# MAXIM-ADC1.net
KiCad netlist of a schematic drawn in Altium Designer
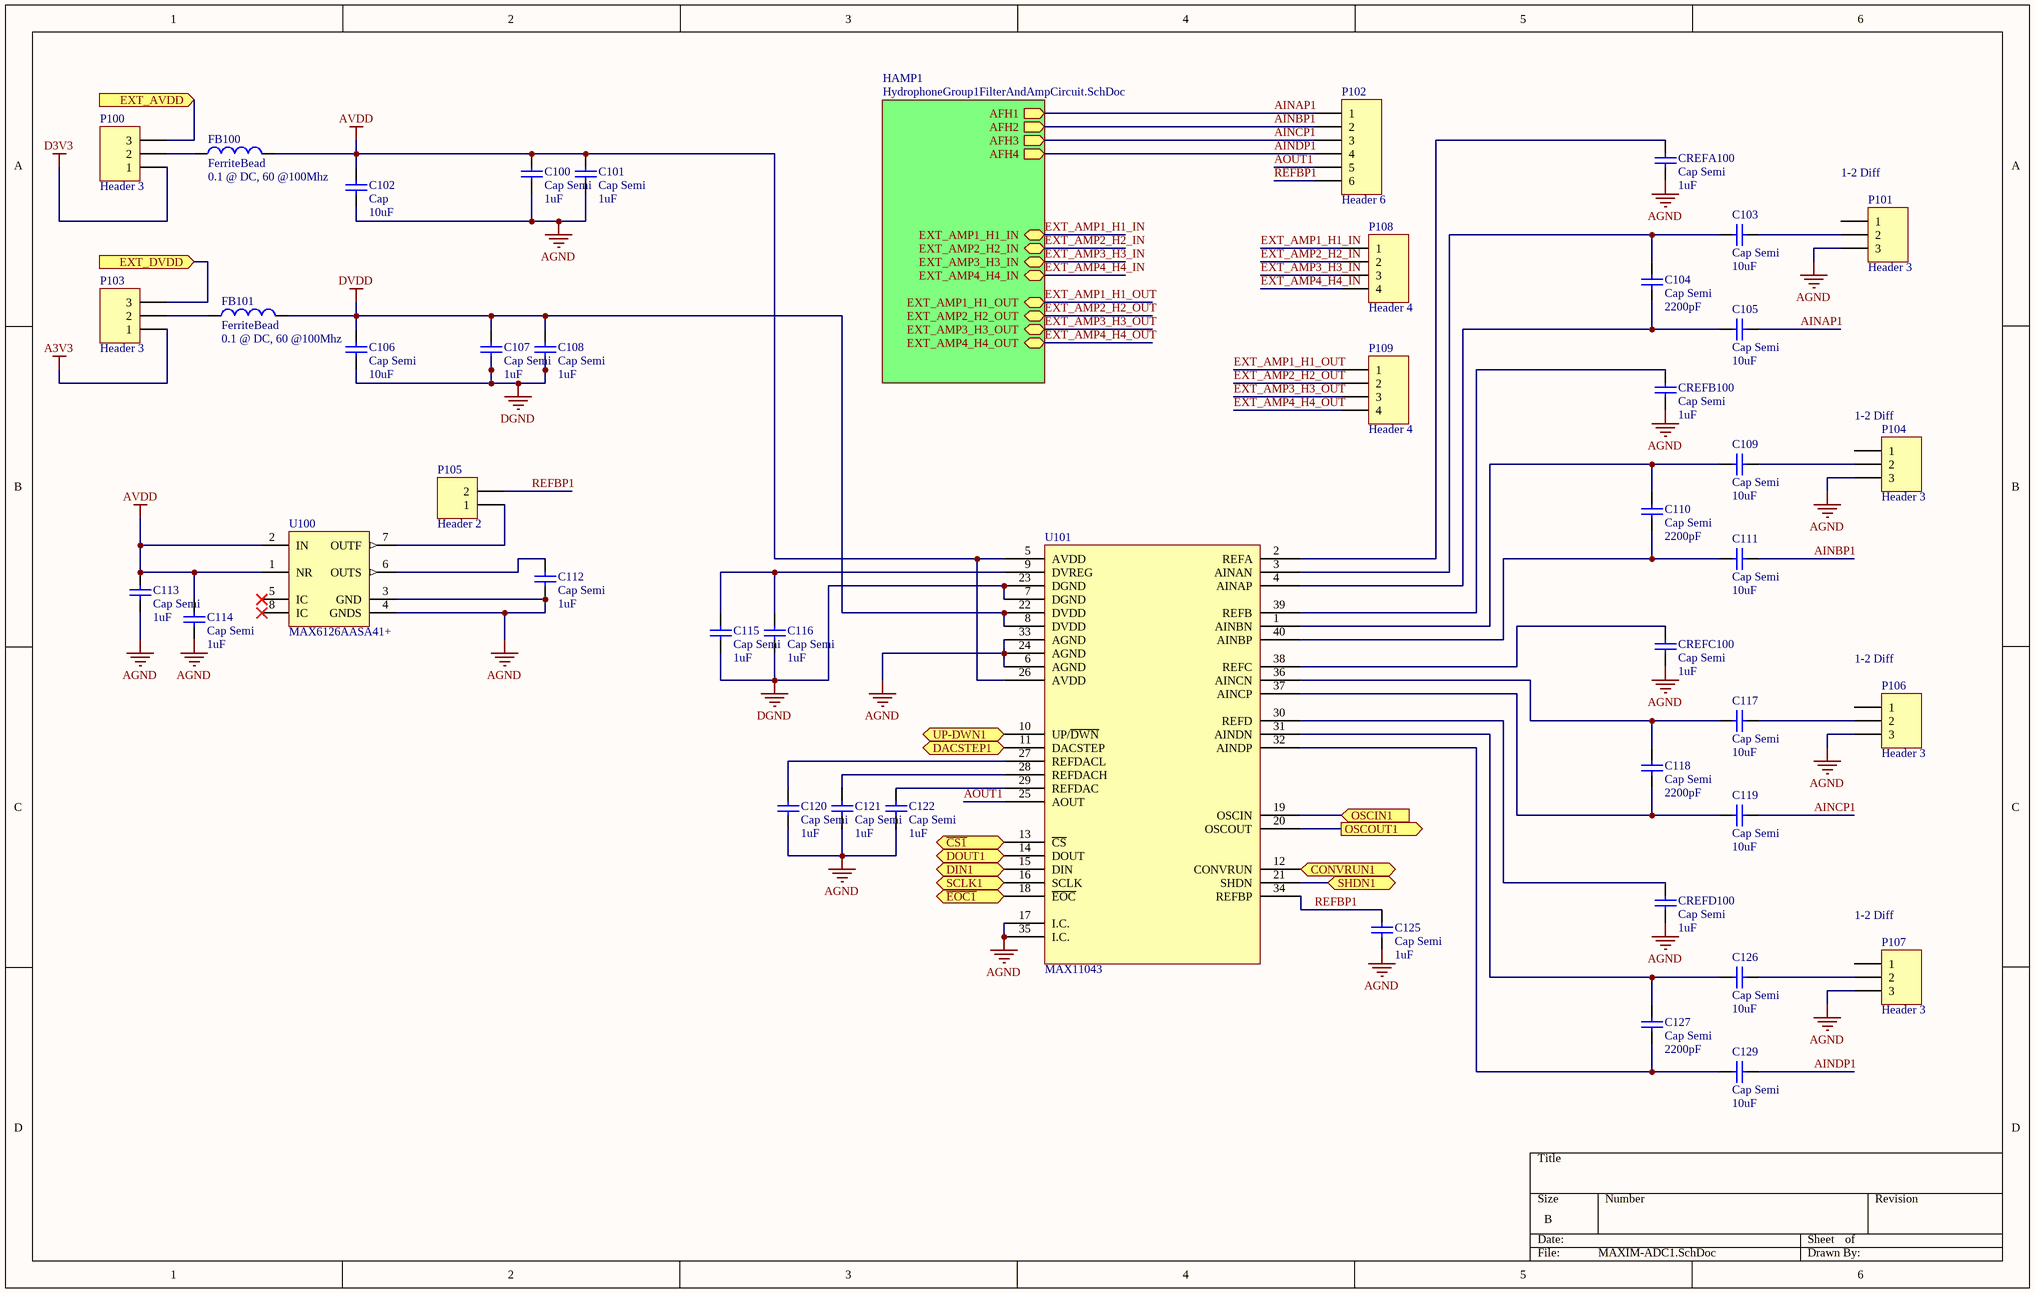
[diagram p0: MAXIM-ADC1.SchDoc]

(export (version "E")
  (design (tool "Eeschema 10.0.6"))
  (components
    (comp (ref "C100")
      (value "Cap Semi")
      (footprint "1608[0603]")
      (description "Capacitor (Semiconductor SIM Model)")
      (fields (field (name "ALTIUM_VALUE") "1uF") (field (name "PUBLISHER") "Altium Limited"))
      (libsource (lib "Miscellaneous Devices") (part "Cap Semi"))
    )
    (comp (ref "C101")
      (value "Cap Semi")
      (footprint "1608[0603]")
      (description "Capacitor (Semiconductor SIM Model)")
      (fields (field (name "ALTIUM_VALUE") "1uF") (field (name "PUBLISHER") "Altium Limited"))
      (libsource (lib "Miscellaneous Devices") (part "Cap Semi"))
    )
    (comp (ref "C102")
      (value "Cap")
      (footprint "1608[0603]")
      (description "Capacitor (Semiconductor SIM Model)")
      (fields (field (name "ALTIUM_VALUE") "10uF") (field (name "PUBLISHER") "Altium Limited"))
      (libsource (lib "Miscellaneous Devices") (part "Cap Semi"))
    )
    (comp (ref "C103")
      (value "Cap Semi")
      (footprint "1608[0603]")
      (description "Capacitor (Semiconductor SIM Model)")
      (fields (field (name "ALTIUM_VALUE") "10uF") (field (name "PUBLISHER") "Altium Limited"))
      (libsource (lib "Miscellaneous Devices") (part "Cap Semi"))
    )
    (comp (ref "C104")
      (value "Cap Semi")
      (footprint "1608[0603]")
      (description "Capacitor (Semiconductor SIM Model)")
      (fields (field (name "ALTIUM_VALUE") "2200pF") (field (name "PUBLISHER") "Altium Limited"))
      (libsource (lib "Miscellaneous Devices") (part "Cap Semi"))
    )
    (comp (ref "C105")
      (value "Cap Semi")
      (footprint "1608[0603]")
      (description "Capacitor (Semiconductor SIM Model)")
      (fields (field (name "ALTIUM_VALUE") "10uF") (field (name "PUBLISHER") "Altium Limited"))
      (libsource (lib "Miscellaneous Devices") (part "Cap Semi"))
    )
    (comp (ref "C106")
      (value "Cap Semi")
      (footprint "C1206")
      (description "Capacitor (Semiconductor SIM Model)")
      (fields (field (name "ALTIUM_VALUE") "10uF") (field (name "PUBLISHER") "Altium Limited"))
      (libsource (lib "Miscellaneous Devices") (part "Cap Semi"))
    )
    (comp (ref "C107")
      (value "Cap Semi")
      (footprint "1608[0603]")
      (description "Capacitor (Semiconductor SIM Model)")
      (fields (field (name "ALTIUM_VALUE") "1uF") (field (name "PUBLISHER") "Altium Limited"))
      (libsource (lib "Miscellaneous Devices") (part "Cap Semi"))
    )
    (comp (ref "C108")
      (value "Cap Semi")
      (footprint "C1206")
      (description "Capacitor (Semiconductor SIM Model)")
      (fields (field (name "ALTIUM_VALUE") "1uF") (field (name "PUBLISHER") "Altium Limited"))
      (libsource (lib "Miscellaneous Devices") (part "Cap Semi"))
    )
    (comp (ref "C109")
      (value "Cap Semi")
      (footprint "1608[0603]")
      (description "Capacitor (Semiconductor SIM Model)")
      (fields (field (name "ALTIUM_VALUE") "10uF") (field (name "PUBLISHER") "Altium Limited"))
      (libsource (lib "Miscellaneous Devices") (part "Cap Semi"))
    )
    (comp (ref "C110")
      (value "Cap Semi")
      (footprint "1608[0603]")
      (description "Capacitor (Semiconductor SIM Model)")
      (fields (field (name "ALTIUM_VALUE") "2200pF") (field (name "PUBLISHER") "Altium Limited"))
      (libsource (lib "Miscellaneous Devices") (part "Cap Semi"))
    )
    (comp (ref "C111")
      (value "Cap Semi")
      (footprint "1608[0603]")
      (description "Capacitor (Semiconductor SIM Model)")
      (fields (field (name "ALTIUM_VALUE") "10uF") (field (name "PUBLISHER") "Altium Limited"))
      (libsource (lib "Miscellaneous Devices") (part "Cap Semi"))
    )
    (comp (ref "C112")
      (value "Cap Semi")
      (footprint "1608[0603]")
      (description "Capacitor (Semiconductor SIM Model)")
      (fields (field (name "ALTIUM_VALUE") "1uF") (field (name "PUBLISHER") "Altium Limited"))
      (libsource (lib "Miscellaneous Devices") (part "Cap Semi"))
    )
    (comp (ref "C113")
      (value "Cap Semi")
      (footprint "1608[0603]")
      (description "Capacitor (Semiconductor SIM Model)")
      (fields (field (name "ALTIUM_VALUE") "1uF") (field (name "PUBLISHER") "Altium Limited"))
      (libsource (lib "Miscellaneous Devices") (part "Cap Semi"))
    )
    (comp (ref "C114")
      (value "Cap Semi")
      (footprint "1608[0603]")
      (description "Capacitor (Semiconductor SIM Model)")
      (fields (field (name "ALTIUM_VALUE") "1uF") (field (name "PUBLISHER") "Altium Limited"))
      (libsource (lib "Miscellaneous Devices") (part "Cap Semi"))
    )
    (comp (ref "C115")
      (value "Cap Semi")
      (footprint "1608[0603]")
      (description "Capacitor (Semiconductor SIM Model)")
      (fields (field (name "ALTIUM_VALUE") "1uF") (field (name "PUBLISHER") "Altium Limited"))
      (libsource (lib "Miscellaneous Devices") (part "Cap Semi"))
    )
    (comp (ref "C116")
      (value "Cap Semi")
      (footprint "1608[0603]")
      (description "Capacitor (Semiconductor SIM Model)")
      (fields (field (name "ALTIUM_VALUE") "1uF") (field (name "PUBLISHER") "Altium Limited"))
      (libsource (lib "Miscellaneous Devices") (part "Cap Semi"))
    )
    (comp (ref "C117")
      (value "Cap Semi")
      (footprint "1608[0603]")
      (description "Capacitor (Semiconductor SIM Model)")
      (fields (field (name "ALTIUM_VALUE") "10uF") (field (name "PUBLISHER") "Altium Limited"))
      (libsource (lib "Miscellaneous Devices") (part "Cap Semi"))
    )
    (comp (ref "C118")
      (value "Cap Semi")
      (footprint "1608[0603]")
      (description "Capacitor (Semiconductor SIM Model)")
      (fields (field (name "ALTIUM_VALUE") "2200pF") (field (name "PUBLISHER") "Altium Limited"))
      (libsource (lib "Miscellaneous Devices") (part "Cap Semi"))
    )
    (comp (ref "C119")
      (value "Cap Semi")
      (footprint "1608[0603]")
      (description "Capacitor (Semiconductor SIM Model)")
      (fields (field (name "ALTIUM_VALUE") "10uF") (field (name "PUBLISHER") "Altium Limited"))
      (libsource (lib "Miscellaneous Devices") (part "Cap Semi"))
    )
    (comp (ref "C120")
      (value "Cap Semi")
      (footprint "1608[0603]")
      (description "Capacitor (Semiconductor SIM Model)")
      (fields (field (name "ALTIUM_VALUE") "1uF") (field (name "PUBLISHER") "Altium Limited"))
      (libsource (lib "Miscellaneous Devices") (part "Cap Semi"))
    )
    (comp (ref "C121")
      (value "Cap Semi")
      (footprint "1608[0603]")
      (description "Capacitor (Semiconductor SIM Model)")
      (fields (field (name "ALTIUM_VALUE") "1uF") (field (name "PUBLISHER") "Altium Limited"))
      (libsource (lib "Miscellaneous Devices") (part "Cap Semi"))
    )
    (comp (ref "C122")
      (value "Cap Semi")
      (footprint "1608[0603]")
      (description "Capacitor (Semiconductor SIM Model)")
      (fields (field (name "ALTIUM_VALUE") "1uF") (field (name "PUBLISHER") "Altium Limited"))
      (libsource (lib "Miscellaneous Devices") (part "Cap Semi"))
    )
    (comp (ref "C125")
      (value "Cap Semi")
      (footprint "1608[0603]")
      (description "Capacitor (Semiconductor SIM Model)")
      (fields (field (name "ALTIUM_VALUE") "1uF") (field (name "PUBLISHER") "Altium Limited"))
      (libsource (lib "Miscellaneous Devices") (part "Cap Semi"))
    )
    (comp (ref "C126")
      (value "Cap Semi")
      (footprint "1608[0603]")
      (description "Capacitor (Semiconductor SIM Model)")
      (fields (field (name "ALTIUM_VALUE") "10uF") (field (name "PUBLISHER") "Altium Limited"))
      (libsource (lib "Miscellaneous Devices") (part "Cap Semi"))
    )
    (comp (ref "C127")
      (value "Cap Semi")
      (footprint "1608[0603]")
      (description "Capacitor (Semiconductor SIM Model)")
      (fields (field (name "ALTIUM_VALUE") "2200pF") (field (name "PUBLISHER") "Altium Limited"))
      (libsource (lib "Miscellaneous Devices") (part "Cap Semi"))
    )
    (comp (ref "C129")
      (value "Cap Semi")
      (footprint "1608[0603]")
      (description "Capacitor (Semiconductor SIM Model)")
      (fields (field (name "ALTIUM_VALUE") "10uF") (field (name "PUBLISHER") "Altium Limited"))
      (libsource (lib "Miscellaneous Devices") (part "Cap Semi"))
    )
    (comp (ref "CREFA100")
      (value "Cap Semi")
      (footprint "1608[0603]")
      (description "Capacitor (Semiconductor SIM Model)")
      (fields (field (name "ALTIUM_VALUE") "1uF") (field (name "PUBLISHER") "Altium Limited"))
      (libsource (lib "Miscellaneous Devices") (part "Cap Semi"))
    )
    (comp (ref "CREFB100")
      (value "Cap Semi")
      (footprint "1608[0603]")
      (description "Capacitor (Semiconductor SIM Model)")
      (fields (field (name "ALTIUM_VALUE") "1uF") (field (name "PUBLISHER") "Altium Limited"))
      (libsource (lib "Miscellaneous Devices") (part "Cap Semi"))
    )
    (comp (ref "CREFC100")
      (value "Cap Semi")
      (footprint "1608[0603]")
      (description "Capacitor (Semiconductor SIM Model)")
      (fields (field (name "ALTIUM_VALUE") "1uF") (field (name "PUBLISHER") "Altium Limited"))
      (libsource (lib "Miscellaneous Devices") (part "Cap Semi"))
    )
    (comp (ref "CREFD100")
      (value "Cap Semi")
      (footprint "1608[0603]")
      (description "Capacitor (Semiconductor SIM Model)")
      (fields (field (name "ALTIUM_VALUE") "1uF") (field (name "PUBLISHER") "Altium Limited"))
      (libsource (lib "Miscellaneous Devices") (part "Cap Semi"))
    )
    (comp (ref "FB100")
      (value "FerriteBead")
      (footprint "0603")
      (description "Inductor")
      (fields
        (field (name "ALTIUM_VALUE") "0.1 @ DC, 60 @100Mhz")
        (field (name "PUBLISHER") "Altium Limited")
      )
      (libsource (lib "Miscellaneous Devices") (part "Inductor"))
    )
    (comp (ref "FB101")
      (value "FerriteBead")
      (footprint "0603")
      (description "Inductor")
      (fields
        (field (name "ALTIUM_VALUE") "0.1 @ DC, 60 @100Mhz")
        (field (name "PUBLISHER") "Altium Limited")
      )
      (libsource (lib "Miscellaneous Devices") (part "Inductor"))
    )
    (comp (ref "P100")
      (value "Header 3")
      (footprint "HDR1X3")
      (description "Header, 3-Pin")
      (fields (field (name "PUBLISHER") "Altium Limited"))
      (libsource (lib "") (part "Header 3_1"))
    )
    (comp (ref "P101")
      (value "Header 3")
      (footprint "HDR1X3")
      (description "Header, 3-Pin")
      (fields (field (name "PUBLISHER") "Altium Limited"))
      (libsource (lib "Miscellaneous Connectors") (part "Header 3"))
    )
    (comp (ref "P102")
      (value "Header 6")
      (footprint "HDR1X6")
      (description "Header, 6-Pin")
      (fields (field (name "PUBLISHER") "Altium Limited"))
      (libsource (lib "Miscellaneous Connectors") (part "Header 6"))
    )
    (comp (ref "P103")
      (value "Header 3")
      (footprint "HDR1X3")
      (description "Header, 3-Pin")
      (fields (field (name "PUBLISHER") "Altium Limited"))
      (libsource (lib "") (part "Header 3_1"))
    )
    (comp (ref "P104")
      (value "Header 3")
      (footprint "HDR1X3")
      (description "Header, 3-Pin")
      (fields (field (name "PUBLISHER") "Altium Limited"))
      (libsource (lib "Miscellaneous Connectors") (part "Header 3"))
    )
    (comp (ref "P105")
      (value "Header 2")
      (footprint "HDR1X2")
      (description "Header, 2-Pin")
      (fields (field (name "PUBLISHER") "Altium Limited"))
      (libsource (lib "Miscellaneous Connectors") (part "Header 2"))
    )
    (comp (ref "P106")
      (value "Header 3")
      (footprint "HDR1X3")
      (description "Header, 3-Pin")
      (fields (field (name "PUBLISHER") "Altium Limited"))
      (libsource (lib "Miscellaneous Connectors") (part "Header 3"))
    )
    (comp (ref "P107")
      (value "Header 3")
      (footprint "HDR1X3")
      (description "Header, 3-Pin")
      (fields (field (name "PUBLISHER") "Altium Limited"))
      (libsource (lib "Miscellaneous Connectors") (part "Header 3"))
    )
    (comp (ref "P108")
      (value "Header 4")
      (footprint "HDR1X4")
      (description "Header, 4-Pin")
      (fields (field (name "PUBLISHER") "Altium Limited"))
      (libsource (lib "Miscellaneous Connectors") (part "Header 4"))
    )
    (comp (ref "P109")
      (value "Header 4")
      (footprint "HDR1X4")
      (description "Header, 4-Pin")
      (fields (field (name "PUBLISHER") "Altium Limited"))
      (libsource (lib "Miscellaneous Connectors") (part "Header 4"))
    )
    (comp (ref "U100")
      (value "MAX6126AASA41+")
      (footprint "MAXM-S8+4_L")
      (fields (field (name "MANUFACTURER") "Maxim"))
      (libsource (lib "Altium Content Vault") (part "CMP-0977-00016-1"))
    )
    (comp (ref "U101")
      (value "MAX11043")
      (footprint "QFN50P600X600X80_HS-41N")
      (libsource (lib "Max11043") (part "MAX11043"))
    )
  )
  (nets
    (net (code "1") (name "/AINAP1") (class "Default")
      (node (ref "C105") (pin "1") (pinfunction "1_1") (pintype "passive"))
      (node (ref "P102") (pin "1") (pinfunction "1_1") (pintype "passive"))
    )
    (net (code "2") (name "/AINBP1") (class "Default")
      (node (ref "C111") (pin "1") (pinfunction "1_1") (pintype "passive"))
      (node (ref "P102") (pin "2") (pinfunction "2_2") (pintype "passive"))
    )
    (net (code "3") (name "/AINCP1") (class "Default")
      (node (ref "C119") (pin "1") (pinfunction "1_1") (pintype "passive"))
      (node (ref "P102") (pin "3") (pinfunction "3_3") (pintype "passive"))
    )
    (net (code "4") (name "/AINDP1") (class "Default")
      (node (ref "C129") (pin "1") (pinfunction "1_1") (pintype "passive"))
      (node (ref "P102") (pin "4") (pinfunction "4_4") (pintype "passive"))
    )
    (net (code "5") (name "/AOUT1") (class "Default")
      (node (ref "P102") (pin "5") (pinfunction "5_5") (pintype "passive"))
      (node (ref "U101") (pin "25") (pinfunction "AOUT_25") (pintype "passive"))
    )
    (net (code "6") (name "/CONVRUN1") (class "Default")
      (node (ref "U101") (pin "12") (pinfunction "CONVRUN_12") (pintype "passive"))
    )
    (net (code "7") (name "/DACSTEP1") (class "Default")
      (node (ref "U101") (pin "11") (pinfunction "DACSTEP_11") (pintype "passive"))
    )
    (net (code "8") (name "/DIN1") (class "Default")
      (node (ref "U101") (pin "15") (pinfunction "DIN_15") (pintype "passive"))
    )
    (net (code "9") (name "/DOUT1") (class "Default")
      (node (ref "U101") (pin "14") (pinfunction "DOUT_14") (pintype "passive"))
    )
    (net (code "10") (name "/EXT_AMP1_H1_IN") (class "Default")
      (node (ref "P108") (pin "1") (pinfunction "1_1") (pintype "passive"))
    )
    (net (code "11") (name "/EXT_AMP1_H1_OUT") (class "Default")
      (node (ref "P109") (pin "1") (pinfunction "1_1") (pintype "passive"))
    )
    (net (code "12") (name "/EXT_AMP2_H2_IN") (class "Default")
      (node (ref "P108") (pin "2") (pinfunction "2_2") (pintype "passive"))
    )
    (net (code "13") (name "/EXT_AMP2_H2_OUT") (class "Default")
      (node (ref "P109") (pin "2") (pinfunction "2_2") (pintype "passive"))
    )
    (net (code "14") (name "/EXT_AMP3_H3_IN") (class "Default")
      (node (ref "P108") (pin "3") (pinfunction "3_3") (pintype "passive"))
    )
    (net (code "15") (name "/EXT_AMP3_H3_OUT") (class "Default")
      (node (ref "P109") (pin "3") (pinfunction "3_3") (pintype "passive"))
    )
    (net (code "16") (name "/EXT_AMP4_H4_IN") (class "Default")
      (node (ref "P108") (pin "4") (pinfunction "4_4") (pintype "passive"))
    )
    (net (code "17") (name "/EXT_AMP4_H4_OUT") (class "Default")
      (node (ref "P109") (pin "4") (pinfunction "4_4") (pintype "passive"))
    )
    (net (code "18") (name "/EXT_AVDD") (class "Default")
      (node (ref "P100") (pin "3") (pinfunction "3_3") (pintype "passive"))
    )
    (net (code "19") (name "/EXT_DVDD") (class "Default")
      (node (ref "P103") (pin "3") (pinfunction "3_3") (pintype "passive"))
    )
    (net (code "20") (name "/OSCIN1") (class "Default")
      (node (ref "U101") (pin "19") (pinfunction "OSCIN_19") (pintype "passive"))
    )
    (net (code "21") (name "/OSCOUT1") (class "Default")
      (node (ref "U101") (pin "20") (pinfunction "OSCOUT_20") (pintype "passive"))
    )
    (net (code "22") (name "/REFBP1") (class "Default")
      (node (ref "C125") (pin "1") (pinfunction "1_1") (pintype "passive"))
      (node (ref "P102") (pin "6") (pinfunction "6_6") (pintype "passive"))
      (node (ref "P105") (pin "2") (pinfunction "2_2") (pintype "passive"))
      (node (ref "U101") (pin "34") (pinfunction "REFBP_34") (pintype "passive"))
    )
    (net (code "23") (name "/SCLK1") (class "Default")
      (node (ref "U101") (pin "16") (pinfunction "SCLK_16") (pintype "passive"))
    )
    (net (code "24") (name "/SHDN1") (class "Default")
      (node (ref "U101") (pin "21") (pinfunction "SHDN_21") (pintype "passive"))
    )
    (net (code "25") (name "/UP-DWN1") (class "Default")
      (node (ref "U101") (pin "10") (pinfunction "UP/~{DWN}_10") (pintype "passive"))
    )
    (net (code "26") (name "/~{CS1}") (class "Default")
      (node (ref "U101") (pin "13") (pinfunction "~{CS}_13") (pintype "passive"))
    )
    (net (code "27") (name "/~{EOC1}") (class "Default")
      (node (ref "U101") (pin "18") (pinfunction "~{EOC}_18") (pintype "passive"))
    )
    (net (code "28") (name "A3V3") (class "Default")
      (node (ref "P103") (pin "1") (pinfunction "1_1") (pintype "passive"))
    )
    (net (code "29") (name "AGND") (class "Default")
      (node (ref "C100") (pin "2") (pinfunction "2_2") (pintype "passive"))
      (node (ref "C101") (pin "2") (pinfunction "2_2") (pintype "passive"))
      (node (ref "C102") (pin "2") (pinfunction "2_2") (pintype "passive"))
      (node (ref "C112") (pin "2") (pinfunction "2_2") (pintype "passive"))
      (node (ref "C113") (pin "2") (pinfunction "2_2") (pintype "passive"))
      (node (ref "C114") (pin "2") (pinfunction "2_2") (pintype "passive"))
      (node (ref "C120") (pin "1") (pinfunction "1_1") (pintype "passive"))
      (node (ref "C121") (pin "2") (pinfunction "2_2") (pintype "passive"))
      (node (ref "C122") (pin "1") (pinfunction "1_1") (pintype "passive"))
      (node (ref "C125") (pin "2") (pinfunction "2_2") (pintype "passive"))
      (node (ref "CREFA100") (pin "1") (pinfunction "1_1") (pintype "passive"))
      (node (ref "CREFB100") (pin "1") (pinfunction "1_1") (pintype "passive"))
      (node (ref "CREFC100") (pin "1") (pinfunction "1_1") (pintype "passive"))
      (node (ref "CREFD100") (pin "1") (pinfunction "1_1") (pintype "passive"))
      (node (ref "P101") (pin "3") (pinfunction "3_3") (pintype "passive"))
      (node (ref "P104") (pin "3") (pinfunction "3_3") (pintype "passive"))
      (node (ref "P106") (pin "3") (pinfunction "3_3") (pintype "passive"))
      (node (ref "P107") (pin "3") (pinfunction "3_3") (pintype "passive"))
      (node (ref "U100") (pin "3") (pinfunction "GND_3") (pintype "power_in"))
      (node (ref "U100") (pin "4") (pinfunction "GNDS_4") (pintype "power_in"))
      (node (ref "U101") (pin "17") (pinfunction "I.C._17") (pintype "passive"))
      (node (ref "U101") (pin "24") (pinfunction "AGND_24") (pintype "passive"))
      (node (ref "U101") (pin "33") (pinfunction "AGND_33") (pintype "passive"))
      (node (ref "U101") (pin "35") (pinfunction "I.C._35") (pintype "passive"))
      (node (ref "U101") (pin "6") (pinfunction "AGND_6") (pintype "passive"))
    )
    (net (code "30") (name "AVDD") (class "Default")
      (node (ref "C100") (pin "1") (pinfunction "1_1") (pintype "passive"))
      (node (ref "C101") (pin "1") (pinfunction "1_1") (pintype "passive"))
      (node (ref "C102") (pin "1") (pinfunction "1_1") (pintype "passive"))
      (node (ref "C113") (pin "1") (pinfunction "1_1") (pintype "passive"))
      (node (ref "C114") (pin "1") (pinfunction "1_1") (pintype "passive"))
      (node (ref "FB100") (pin "2") (pinfunction "2_2") (pintype "passive"))
      (node (ref "U100") (pin "1") (pinfunction "NR_1") (pintype "passive"))
      (node (ref "U100") (pin "2") (pinfunction "IN_2") (pintype "power_in"))
      (node (ref "U101") (pin "26") (pinfunction "AVDD_26") (pintype "passive"))
      (node (ref "U101") (pin "5") (pinfunction "AVDD_5") (pintype "passive"))
    )
    (net (code "31") (name "D3V3") (class "Default")
      (node (ref "P100") (pin "1") (pinfunction "1_1") (pintype "passive"))
    )
    (net (code "32") (name "DGND") (class "Default")
      (node (ref "C106") (pin "2") (pinfunction "2_2") (pintype "passive"))
      (node (ref "C107") (pin "2") (pinfunction "2_2") (pintype "passive"))
      (node (ref "C108") (pin "2") (pinfunction "2_2") (pintype "passive"))
      (node (ref "C115") (pin "2") (pinfunction "2_2") (pintype "passive"))
      (node (ref "C116") (pin "2") (pinfunction "2_2") (pintype "passive"))
      (node (ref "U101") (pin "23") (pinfunction "DGND_23") (pintype "passive"))
      (node (ref "U101") (pin "7") (pinfunction "DGND_7") (pintype "passive"))
    )
    (net (code "33") (name "DVDD") (class "Default")
      (node (ref "C106") (pin "1") (pinfunction "1_1") (pintype "passive"))
      (node (ref "C107") (pin "1") (pinfunction "1_1") (pintype "passive"))
      (node (ref "C108") (pin "1") (pinfunction "1_1") (pintype "passive"))
      (node (ref "FB101") (pin "2") (pinfunction "2_2") (pintype "passive"))
      (node (ref "U101") (pin "22") (pinfunction "DVDD_22") (pintype "passive"))
      (node (ref "U101") (pin "8") (pinfunction "DVDD_8") (pintype "passive"))
    )
    (net (code "34") (name "Net-(C103-Pad1)") (class "Default")
      (node (ref "C103") (pin "1") (pinfunction "1_1") (pintype "passive"))
      (node (ref "P101") (pin "2") (pinfunction "2_2") (pintype "passive"))
    )
    (net (code "35") (name "Net-(C109-Pad1)") (class "Default")
      (node (ref "C109") (pin "1") (pinfunction "1_1") (pintype "passive"))
      (node (ref "P104") (pin "2") (pinfunction "2_2") (pintype "passive"))
    )
    (net (code "36") (name "Net-(C117-Pad1)") (class "Default")
      (node (ref "C117") (pin "1") (pinfunction "1_1") (pintype "passive"))
      (node (ref "P106") (pin "2") (pinfunction "2_2") (pintype "passive"))
    )
    (net (code "37") (name "Net-(C126-Pad1)") (class "Default")
      (node (ref "C126") (pin "1") (pinfunction "1_1") (pintype "passive"))
      (node (ref "P107") (pin "2") (pinfunction "2_2") (pintype "passive"))
    )
    (net (code "38") (name "Net-(FB100-Pad1)") (class "Default")
      (node (ref "FB100") (pin "1") (pinfunction "1_1") (pintype "passive"))
      (node (ref "P100") (pin "2") (pinfunction "2_2") (pintype "passive"))
    )
    (net (code "39") (name "Net-(FB101-Pad1)") (class "Default")
      (node (ref "FB101") (pin "1") (pinfunction "1_1") (pintype "passive"))
      (node (ref "P103") (pin "2") (pinfunction "2_2") (pintype "passive"))
    )
    (net (code "40") (name "Net-(U100-OUTF)") (class "Default")
      (node (ref "P105") (pin "1") (pinfunction "1_1") (pintype "passive"))
      (node (ref "U100") (pin "7") (pinfunction "OUTF_7") (pintype "output"))
    )
    (net (code "41") (name "Net-(U100-OUTS)") (class "Default")
      (node (ref "C112") (pin "1") (pinfunction "1_1") (pintype "passive"))
      (node (ref "U100") (pin "6") (pinfunction "OUTS_6") (pintype "output"))
    )
    (net (code "42") (name "Net-(U101-AINAN)") (class "Default")
      (node (ref "C103") (pin "2") (pinfunction "2_2") (pintype "passive"))
      (node (ref "C104") (pin "2") (pinfunction "2_2") (pintype "passive"))
      (node (ref "U101") (pin "3") (pinfunction "AINAN_3") (pintype "passive"))
    )
    (net (code "43") (name "Net-(U101-AINAP)") (class "Default")
      (node (ref "C104") (pin "1") (pinfunction "1_1") (pintype "passive"))
      (node (ref "C105") (pin "2") (pinfunction "2_2") (pintype "passive"))
      (node (ref "U101") (pin "4") (pinfunction "AINAP_4") (pintype "passive"))
    )
    (net (code "44") (name "Net-(U101-AINBN)") (class "Default")
      (node (ref "C109") (pin "2") (pinfunction "2_2") (pintype "passive"))
      (node (ref "C110") (pin "2") (pinfunction "2_2") (pintype "passive"))
      (node (ref "U101") (pin "1") (pinfunction "AINBN_1") (pintype "passive"))
    )
    (net (code "45") (name "Net-(U101-AINBP)") (class "Default")
      (node (ref "C110") (pin "1") (pinfunction "1_1") (pintype "passive"))
      (node (ref "C111") (pin "2") (pinfunction "2_2") (pintype "passive"))
      (node (ref "U101") (pin "40") (pinfunction "AINBP_40") (pintype "passive"))
    )
    (net (code "46") (name "Net-(U101-AINCN)") (class "Default")
      (node (ref "C117") (pin "2") (pinfunction "2_2") (pintype "passive"))
      (node (ref "C118") (pin "2") (pinfunction "2_2") (pintype "passive"))
      (node (ref "U101") (pin "36") (pinfunction "AINCN_36") (pintype "passive"))
    )
    (net (code "47") (name "Net-(U101-AINCP)") (class "Default")
      (node (ref "C118") (pin "1") (pinfunction "1_1") (pintype "passive"))
      (node (ref "C119") (pin "2") (pinfunction "2_2") (pintype "passive"))
      (node (ref "U101") (pin "37") (pinfunction "AINCP_37") (pintype "passive"))
    )
    (net (code "48") (name "Net-(U101-AINDN)") (class "Default")
      (node (ref "C126") (pin "2") (pinfunction "2_2") (pintype "passive"))
      (node (ref "C127") (pin "2") (pinfunction "2_2") (pintype "passive"))
      (node (ref "U101") (pin "31") (pinfunction "AINDN_31") (pintype "passive"))
    )
    (net (code "49") (name "Net-(U101-AINDP)") (class "Default")
      (node (ref "C127") (pin "1") (pinfunction "1_1") (pintype "passive"))
      (node (ref "C129") (pin "2") (pinfunction "2_2") (pintype "passive"))
      (node (ref "U101") (pin "32") (pinfunction "AINDP_32") (pintype "passive"))
    )
    (net (code "50") (name "Net-(U101-DVREG)") (class "Default")
      (node (ref "C115") (pin "1") (pinfunction "1_1") (pintype "passive"))
      (node (ref "C116") (pin "1") (pinfunction "1_1") (pintype "passive"))
      (node (ref "U101") (pin "9") (pinfunction "DVREG_9") (pintype "passive"))
    )
    (net (code "51") (name "Net-(U101-REFA)") (class "Default")
      (node (ref "CREFA100") (pin "2") (pinfunction "2_2") (pintype "passive"))
      (node (ref "U101") (pin "2") (pinfunction "REFA_2") (pintype "passive"))
    )
    (net (code "52") (name "Net-(U101-REFB)") (class "Default")
      (node (ref "CREFB100") (pin "2") (pinfunction "2_2") (pintype "passive"))
      (node (ref "U101") (pin "39") (pinfunction "REFB_39") (pintype "passive"))
    )
    (net (code "53") (name "Net-(U101-REFC)") (class "Default")
      (node (ref "CREFC100") (pin "2") (pinfunction "2_2") (pintype "passive"))
      (node (ref "U101") (pin "38") (pinfunction "REFC_38") (pintype "passive"))
    )
    (net (code "54") (name "Net-(U101-REFD)") (class "Default")
      (node (ref "CREFD100") (pin "2") (pinfunction "2_2") (pintype "passive"))
      (node (ref "U101") (pin "30") (pinfunction "REFD_30") (pintype "passive"))
    )
    (net (code "55") (name "Net-(U101-REFDAC)") (class "Default")
      (node (ref "C122") (pin "2") (pinfunction "2_2") (pintype "passive"))
      (node (ref "U101") (pin "29") (pinfunction "REFDAC_29") (pintype "passive"))
    )
    (net (code "56") (name "Net-(U101-REFDACH)") (class "Default")
      (node (ref "C121") (pin "1") (pinfunction "1_1") (pintype "passive"))
      (node (ref "U101") (pin "28") (pinfunction "REFDACH_28") (pintype "passive"))
    )
    (net (code "57") (name "Net-(U101-REFDACL)") (class "Default")
      (node (ref "C120") (pin "2") (pinfunction "2_2") (pintype "passive"))
      (node (ref "U101") (pin "27") (pinfunction "REFDACL_27") (pintype "passive"))
    )
    (net (code "58") (name "unconnected-(P101-Pad1)") (class "Default")
      (node (ref "P101") (pin "1") (pinfunction "1_1") (pintype "passive"))
    )
    (net (code "59") (name "unconnected-(P104-Pad1)") (class "Default")
      (node (ref "P104") (pin "1") (pinfunction "1_1") (pintype "passive"))
    )
    (net (code "60") (name "unconnected-(P106-Pad1)") (class "Default")
      (node (ref "P106") (pin "1") (pinfunction "1_1") (pintype "passive"))
    )
    (net (code "61") (name "unconnected-(P107-Pad1)") (class "Default")
      (node (ref "P107") (pin "1") (pinfunction "1_1") (pintype "passive"))
    )
    (net (code "62") (name "unconnected-(U100-IC-Pad5)") (class "Default")
      (node (ref "U100") (pin "5") (pinfunction "IC_5") (pintype "passive+no_connect"))
    )
    (net (code "63") (name "unconnected-(U100-IC-Pad8)") (class "Default")
      (node (ref "U100") (pin "8") (pinfunction "IC_8") (pintype "passive+no_connect"))
    )
  )
)
